# Erica-HAT.net
KiCad netlist of a schematic drawn in EAGLE
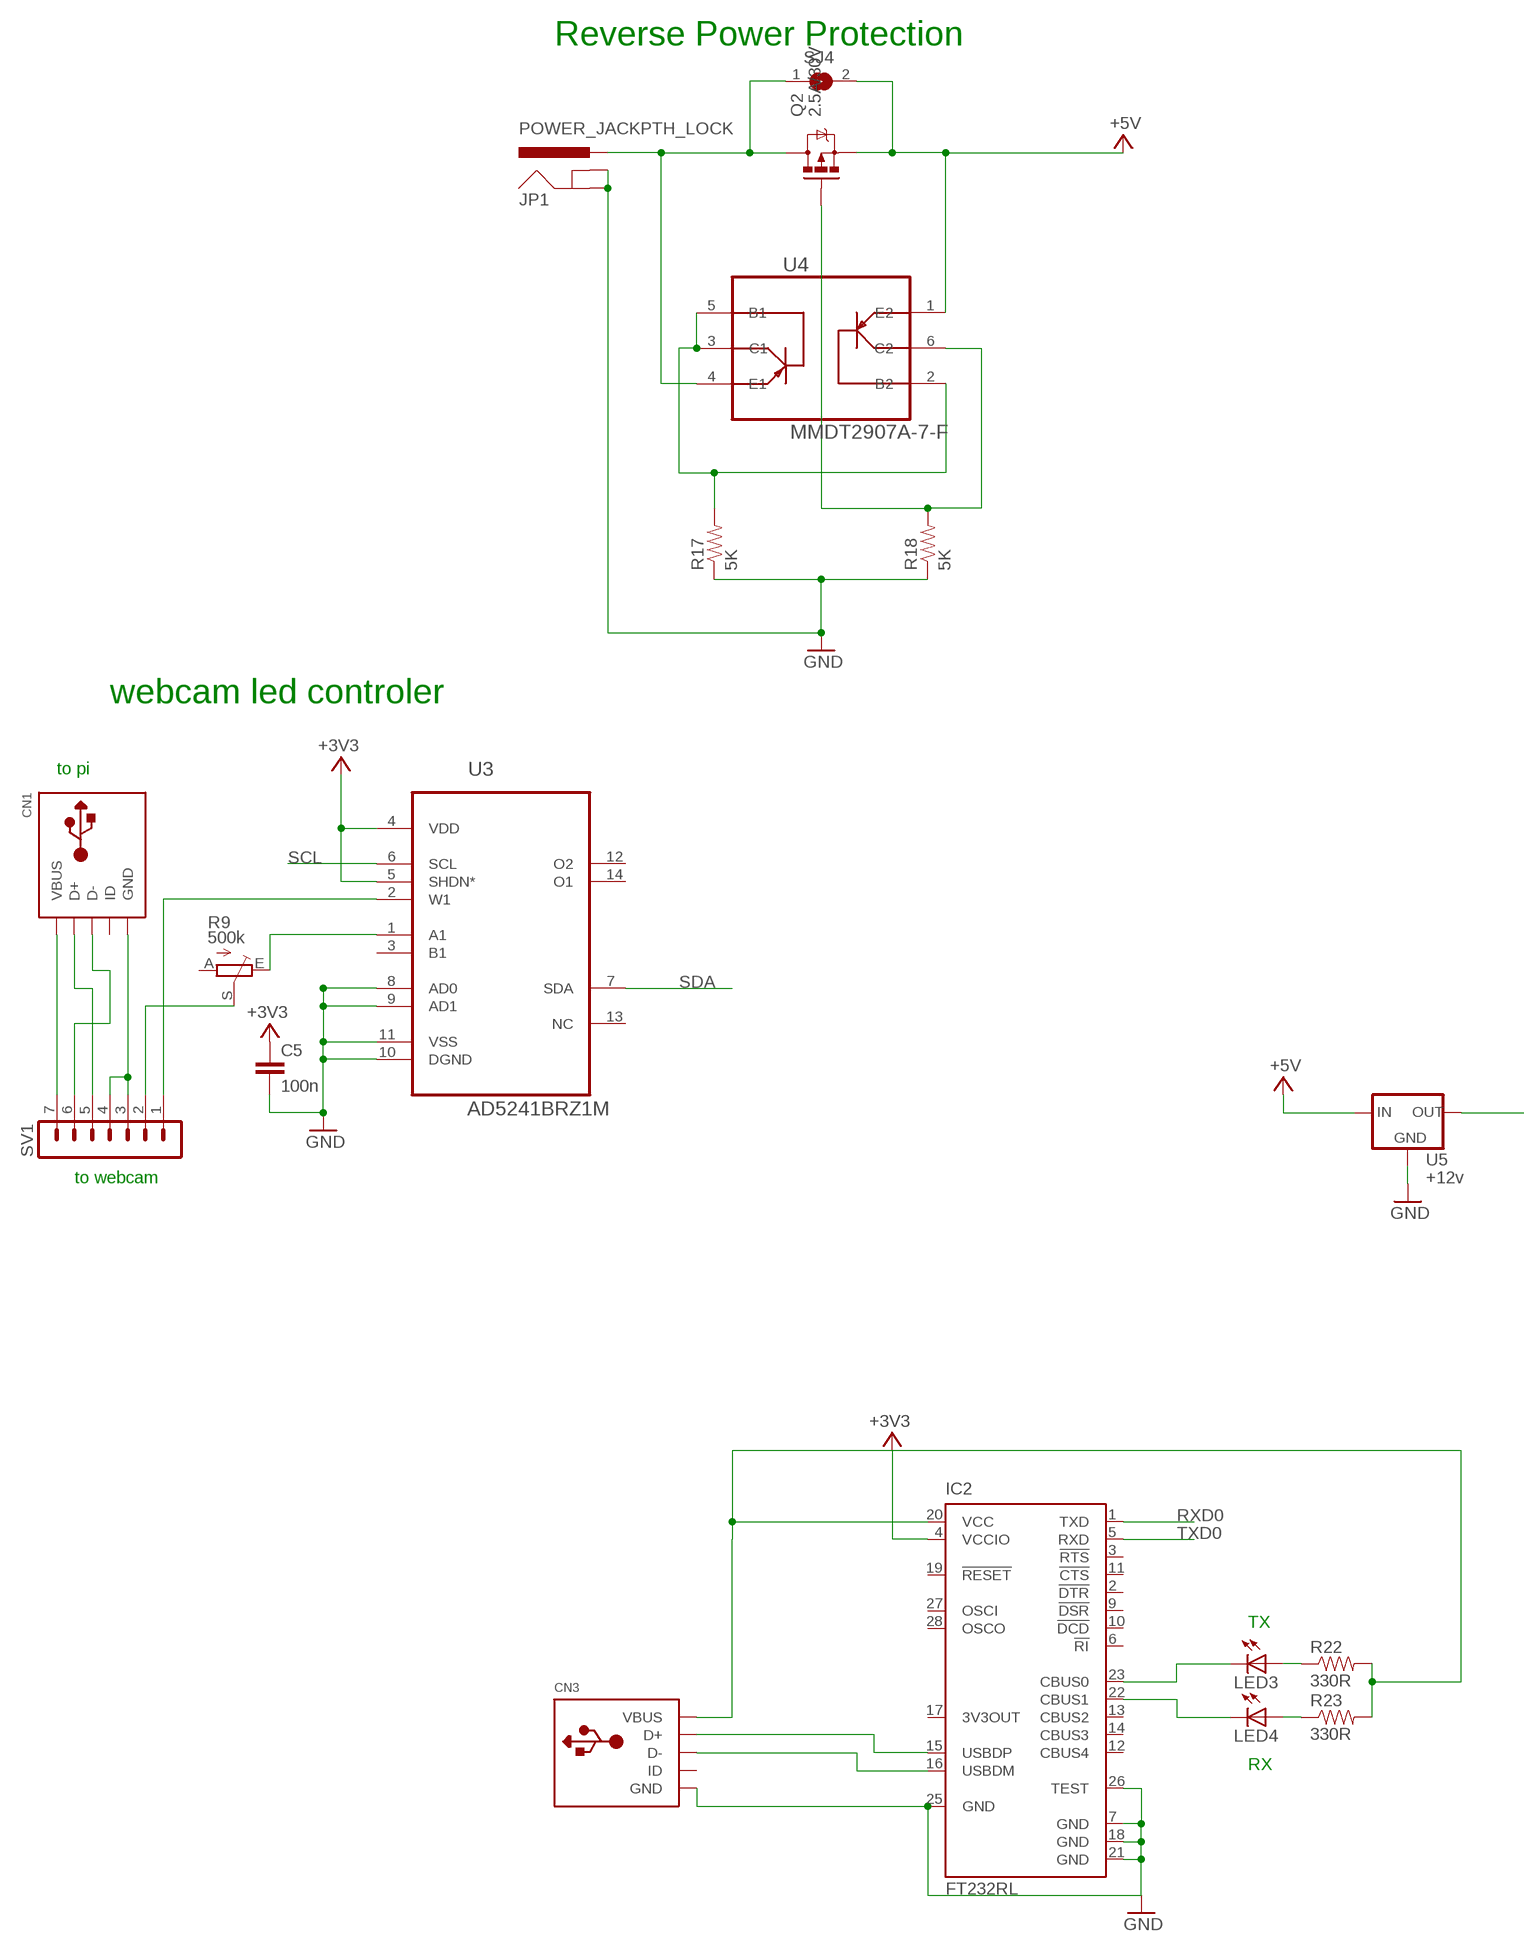
[diagram p0: schematic, sheet 1, part 1 of 2]
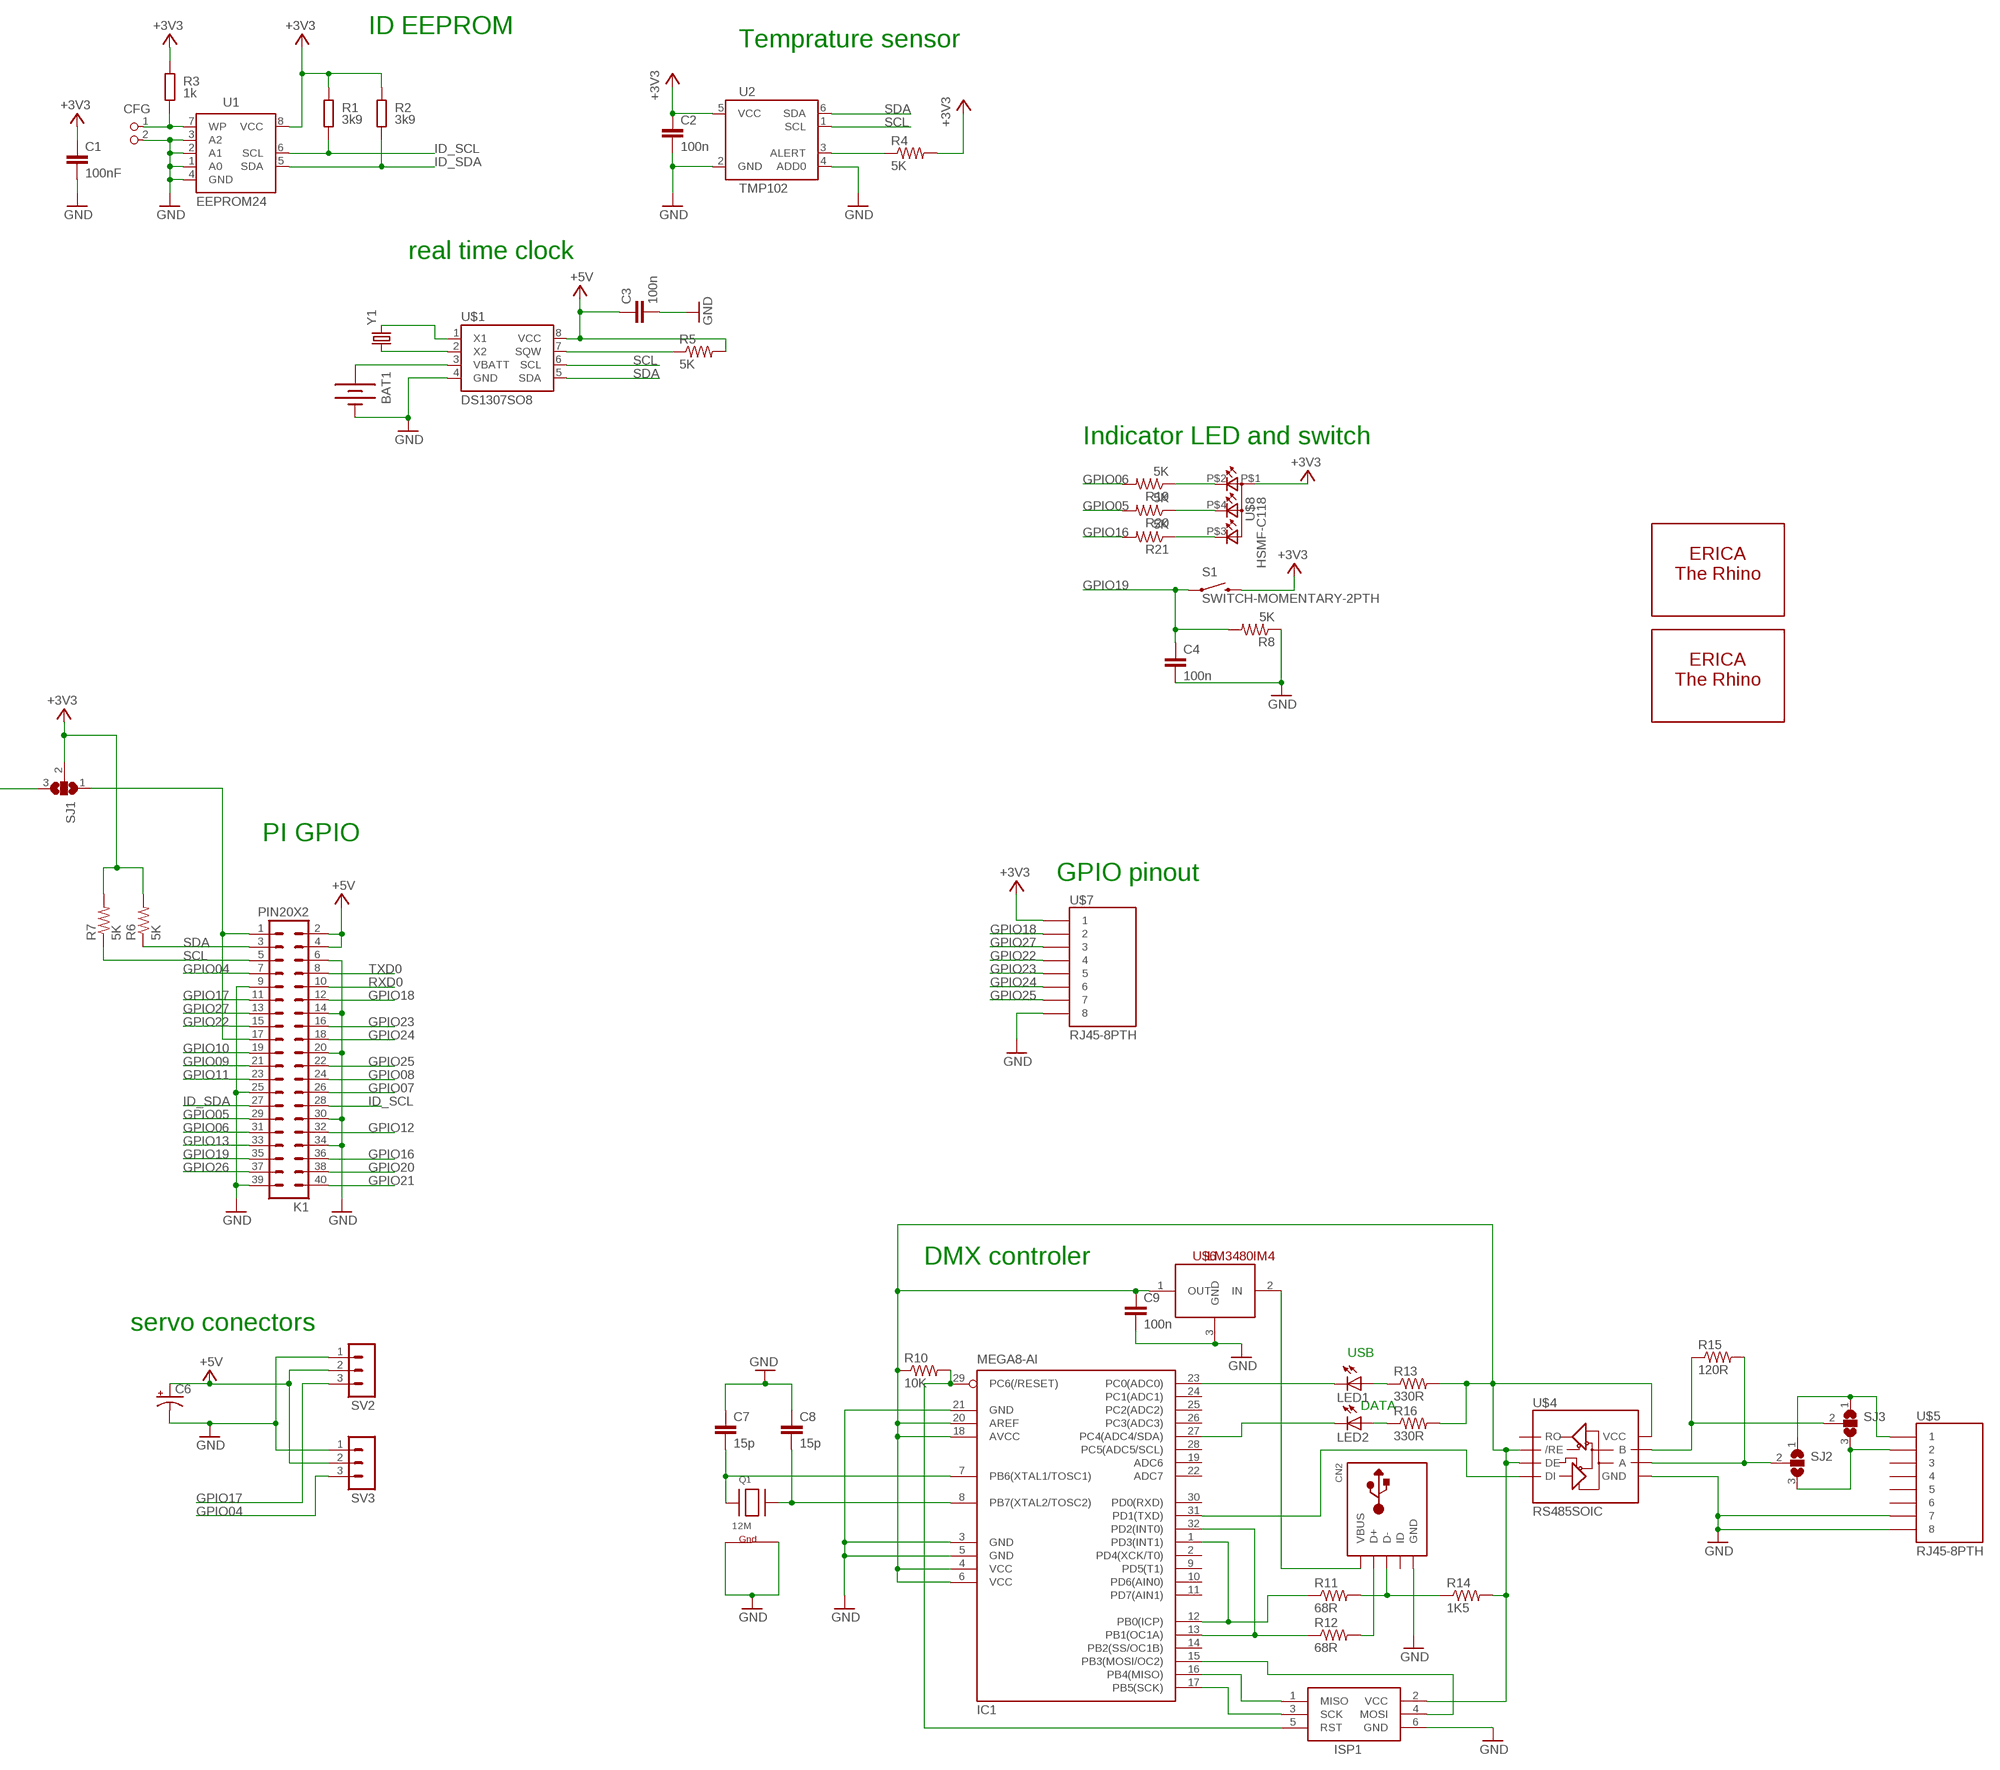
[diagram p1: schematic, sheet 1, part 2 of 2]

(export (version "E")
  (design (tool "Eeschema 10.0.6"))
  (components
    (comp (ref "BAT1")
      (value "BATTERY12MM")
      (footprint "eagle-import:BATTCON_12MM")
      (libsource (lib "eagle-import") (part "BATTERY12MM"))
    )
    (comp (ref "C1")
      (value "100nF")
      (footprint "eagle-import:C0805K")
      (libsource (lib "eagle-import") (part "C-EUC0805K"))
    )
    (comp (ref "C2")
      (value "100n")
      (footprint "eagle-import:0603-CAP")
      (libsource (lib "eagle-import") (part "CAP0603-CAP"))
    )
    (comp (ref "C3")
      (value "100n")
      (footprint "eagle-import:0603-CAP")
      (libsource (lib "eagle-import") (part "CAP0603-CAP"))
    )
    (comp (ref "C4")
      (value "100n")
      (footprint "eagle-import:0603-CAP")
      (libsource (lib "eagle-import") (part "CAP0603-CAP"))
    )
    (comp (ref "C5")
      (value "100n")
      (footprint "eagle-import:0603-CAP")
      (libsource (lib "eagle-import") (part "CAP0603-CAP"))
    )
    (comp (ref "C6")
      (value "CAP_POLPTH2")
      (footprint "eagle-import:CPOL-RADIAL-10UF-25V")
      (libsource (lib "eagle-import") (part "CAP_POLPTH2"))
    )
    (comp (ref "C7")
      (value "15p")
      (footprint "eagle-import:0603-CAP")
      (libsource (lib "eagle-import") (part "CAP0603-CAP"))
    )
    (comp (ref "C8")
      (value "15p")
      (footprint "eagle-import:0603-CAP")
      (libsource (lib "eagle-import") (part "CAP0603-CAP"))
    )
    (comp (ref "C9")
      (value "100n")
      (footprint "eagle-import:0603-CAP")
      (libsource (lib "eagle-import") (part "CAP0603-CAP"))
    )
    (comp (ref "CFG")
      (value "PIN2_100")
      (footprint "eagle-import:PIN_W_2")
      (libsource (lib "eagle-import") (part "PIN2_100"))
    )
    (comp (ref "CN1")
      (value "USBMINIB")
      (footprint "eagle-import:USB-MINIB")
      (libsource (lib "eagle-import") (part "USBMINIB"))
    )
    (comp (ref "CN2")
      (value "USBMINIB")
      (footprint "eagle-import:USB-MINIB")
      (libsource (lib "eagle-import") (part "USBMINIB"))
    )
    (comp (ref "CN3")
      (value "USBMINIB")
      (footprint "eagle-import:USB-MINIB")
      (libsource (lib "eagle-import") (part "USBMINIB"))
    )
    (comp (ref "IC1")
      (value "MEGA8-AI")
      (footprint "eagle-import:TQFP32-08")
      (fields (field (name "MPN") "ATMEGA8-16AU"))
      (libsource (lib "eagle-import") (part "MEGA8-AI"))
    )
    (comp (ref "IC2")
      (value "FT232RL")
      (footprint "eagle-import:SSOP28")
      (libsource (lib "eagle-import") (part "FT232RL"))
    )
    (comp (ref "ISP1")
      (value "AVRISP-6")
      (footprint "eagle-import:AVRISP")
      (libsource (lib "eagle-import") (part "AVRISP-6"))
    )
    (comp (ref "JP1")
      (value "POWER_JACKPTH_LOCK")
      (footprint "eagle-import:POWER_JACK_PTH_LOCK")
      (libsource (lib "eagle-import") (part "POWER_JACKPTH_LOCK"))
    )
    (comp (ref "K1")
      (value "PIN20X2")
      (footprint "eagle-import:PIN_20X2")
      (libsource (lib "eagle-import") (part "PIN20X2"))
    )
    (comp (ref "LED1")
      (value "LEDCHIP-LED0603")
      (footprint "eagle-import:CHIP-LED0603")
      (libsource (lib "eagle-import") (part "LEDCHIP-LED0603"))
    )
    (comp (ref "LED2")
      (value "LEDCHIP-LED0603")
      (footprint "eagle-import:CHIP-LED0603")
      (libsource (lib "eagle-import") (part "LEDCHIP-LED0603"))
    )
    (comp (ref "LED3")
      (value "LEDCHIP-LED0603")
      (footprint "eagle-import:CHIP-LED0603")
      (libsource (lib "eagle-import") (part "LEDCHIP-LED0603"))
    )
    (comp (ref "LED4")
      (value "LEDCHIP-LED0603")
      (footprint "eagle-import:CHIP-LED0603")
      (libsource (lib "eagle-import") (part "LEDCHIP-LED0603"))
    )
    (comp (ref "Q1")
      (value "12M")
      (footprint "eagle-import:NX3225")
      (libsource (lib "eagle-import") (part "XTAL-4-3225"))
    )
    (comp (ref "Q2")
      (value "2.5A/30V")
      (footprint "eagle-import:SOT23-3")
      (libsource (lib "eagle-import") (part "MOSFET-PCHANNELDMG2307L"))
    )
    (comp (ref "R1")
      (value "3k9")
      (footprint "eagle-import:M0805")
      (fields (field (name "TOLERANCE") "5%"))
      (libsource (lib "eagle-import") (part "R-EU_M0805"))
    )
    (comp (ref "R2")
      (value "3k9")
      (footprint "eagle-import:M0805")
      (fields (field (name "TOLERANCE") "5%"))
      (libsource (lib "eagle-import") (part "R-EU_M0805"))
    )
    (comp (ref "R3")
      (value "1k")
      (footprint "eagle-import:M0805")
      (fields (field (name "TOLERANCE") "5%"))
      (libsource (lib "eagle-import") (part "R-EU_M0805"))
    )
    (comp (ref "R4")
      (value "5K")
      (footprint "eagle-import:0603-RES")
      (libsource (lib "eagle-import") (part "RESISTOR0603-RES"))
    )
    (comp (ref "R5")
      (value "5K")
      (footprint "eagle-import:0603-RES")
      (libsource (lib "eagle-import") (part "RESISTOR0603-RES"))
    )
    (comp (ref "R6")
      (value "5K")
      (footprint "eagle-import:0603-RES")
      (libsource (lib "eagle-import") (part "RESISTOR0603-RES"))
    )
    (comp (ref "R7")
      (value "5K")
      (footprint "eagle-import:0603-RES")
      (libsource (lib "eagle-import") (part "RESISTOR0603-RES"))
    )
    (comp (ref "R8")
      (value "5K")
      (footprint "eagle-import:0603-RES")
      (libsource (lib "eagle-import") (part "RESISTOR0603-RES"))
    )
    (comp (ref "R9")
      (value "500k")
      (footprint "eagle-import:B25U")
      (libsource (lib "eagle-import") (part "TRIM_EU-B25U"))
    )
    (comp (ref "R10")
      (value "10K")
      (footprint "eagle-import:0603-RES")
      (libsource (lib "eagle-import") (part "RESISTOR0603-RES"))
    )
    (comp (ref "R11")
      (value "68R")
      (footprint "eagle-import:0603-RES")
      (libsource (lib "eagle-import") (part "RESISTOR0603-RES"))
    )
    (comp (ref "R12")
      (value "68R")
      (footprint "eagle-import:0603-RES")
      (libsource (lib "eagle-import") (part "RESISTOR0603-RES"))
    )
    (comp (ref "R13")
      (value "330R")
      (footprint "eagle-import:0603-RES")
      (libsource (lib "eagle-import") (part "RESISTOR0603-RES"))
    )
    (comp (ref "R14")
      (value "1K5")
      (footprint "eagle-import:0603-RES")
      (libsource (lib "eagle-import") (part "RESISTOR0603-RES"))
    )
    (comp (ref "R15")
      (value "120R")
      (footprint "eagle-import:0603-RES")
      (libsource (lib "eagle-import") (part "RESISTOR0603-RES"))
    )
    (comp (ref "R16")
      (value "330R")
      (footprint "eagle-import:0603-RES")
      (libsource (lib "eagle-import") (part "RESISTOR0603-RES"))
    )
    (comp (ref "R17")
      (value "5K")
      (footprint "eagle-import:0603-RES")
      (libsource (lib "eagle-import") (part "RESISTOR0603-RES"))
    )
    (comp (ref "R18")
      (value "5K")
      (footprint "eagle-import:0603-RES")
      (libsource (lib "eagle-import") (part "RESISTOR0603-RES"))
    )
    (comp (ref "R19")
      (value "5K")
      (footprint "eagle-import:0603-RES")
      (libsource (lib "eagle-import") (part "RESISTOR0603-RES"))
    )
    (comp (ref "R20")
      (value "5K")
      (footprint "eagle-import:0603-RES")
      (libsource (lib "eagle-import") (part "RESISTOR0603-RES"))
    )
    (comp (ref "R21")
      (value "5K")
      (footprint "eagle-import:0603-RES")
      (libsource (lib "eagle-import") (part "RESISTOR0603-RES"))
    )
    (comp (ref "R22")
      (value "330R")
      (footprint "eagle-import:0603-RES")
      (libsource (lib "eagle-import") (part "RESISTOR0603-RES"))
    )
    (comp (ref "R23")
      (value "330R")
      (footprint "eagle-import:0603-RES")
      (libsource (lib "eagle-import") (part "RESISTOR0603-RES"))
    )
    (comp (ref "S1")
      (value "SWITCH-MOMENTARY-2PTH")
      (footprint "eagle-import:TACTILE-PTH")
      (libsource (lib "eagle-import") (part "SWITCH-MOMENTARY-2PTH"))
    )
    (comp (ref "SJ1")
      (value "SJ2W")
      (footprint "eagle-import:SJ_2")
      (libsource (lib "eagle-import") (part "SJ2W"))
    )
    (comp (ref "SJ2")
      (value "SJ2W")
      (footprint "eagle-import:SJ_2")
      (libsource (lib "eagle-import") (part "SJ2W"))
    )
    (comp (ref "SJ3")
      (value "SJ2W")
      (footprint "eagle-import:SJ_2")
      (libsource (lib "eagle-import") (part "SJ2W"))
    )
    (comp (ref "SJ4") (value "SJ") (footprint "eagle-import:SJ") (libsource (lib "eagle-import") (part "SJ")))
    (comp (ref "SV1")
      (value "MA07-1")
      (footprint "eagle-import:MA07-1")
      (libsource (lib "eagle-import") (part "MA07-1"))
    )
    (comp (ref "SV2")
      (value "MA03-1")
      (footprint "eagle-import:MA03-1")
      (libsource (lib "eagle-import") (part "MA03-1"))
    )
    (comp (ref "SV3")
      (value "MA03-1")
      (footprint "eagle-import:MA03-1")
      (libsource (lib "eagle-import") (part "MA03-1"))
    )
    (comp (ref "U$1")
      (value "DS1307SO8")
      (footprint "eagle-import:SO08")
      (libsource (lib "eagle-import") (part "DS1307SO8"))
    )
    (comp (ref "U$2")
      (value "ERICALOGO")
      (footprint "eagle-import:ERICA_LOGO")
      (libsource (lib "eagle-import") (part "ERICALOGO"))
    )
    (comp (ref "U$3")
      (value "ERICASILHOUETTE")
      (footprint "eagle-import:ERICA_SILHOUETTE")
      (libsource (lib "eagle-import") (part "ERICASILHOUETTE"))
    )
    (comp (ref "U$4")
      (value "RS485SOIC")
      (footprint "eagle-import:SO08")
      (libsource (lib "eagle-import") (part "RS485SOIC"))
    )
    (comp (ref "U$5")
      (value "RJ45-8PTH")
      (footprint "eagle-import:RJ45-8")
      (libsource (lib "eagle-import") (part "RJ45-8PTH"))
    )
    (comp (ref "U$6")
      (value "LM3480IM4")
      (footprint "eagle-import:SOT23-3")
      (libsource (lib "eagle-import") (part "LM3480IM4"))
    )
    (comp (ref "U$7")
      (value "RJ45-8PTH")
      (footprint "eagle-import:RJ45-8")
      (libsource (lib "eagle-import") (part "RJ45-8PTH"))
    )
    (comp (ref "U$8")
      (value "HSMF-C118")
      (footprint "eagle-import:HSMF-C118")
      (libsource (lib "eagle-import") (part "HSMF-C118"))
    )
    (comp (ref "U1")
      (value "EEPROM24")
      (footprint "eagle-import:SOIC8")
      (libsource (lib "eagle-import") (part "EEPROM24"))
    )
    (comp (ref "U2")
      (value "TMP102")
      (footprint "eagle-import:SOT563")
      (libsource (lib "eagle-import") (part "TMP102"))
    )
    (comp (ref "U3")
      (value "AD5241BRZ1M")
      (footprint "eagle-import:SOIC127P600X175-14N")
      (libsource (lib "eagle-import") (part "AD5241BRZ1M"))
    )
    (comp (ref "U4")
      (value "MMDT2907A-7-F")
      (footprint "eagle-import:SOT65P210X110-6N")
      (libsource (lib "eagle-import") (part "MMDT2907A-7-F"))
    )
    (comp (ref "U5")
      (value "+12v")
      (footprint "eagle-import:SOT223")
      (libsource (lib "eagle-import") (part "V_REG_MIC2920"))
    )
    (comp (ref "Y1")
      (value "CRYSTAL32-SMD")
      (footprint "eagle-import:CRYSTAL-32KHZ-SMD")
      (libsource (lib "eagle-import") (part "CRYSTAL32-SMD"))
    )
  )
  (nets
    (net (code "1") (name "+3V3") (class "Default")
      (node (ref "C1") (pin "1") (pinfunction "1_1") (pintype "passive"))
      (node (ref "C2") (pin "1") (pinfunction "1_1") (pintype "passive"))
      (node (ref "C5") (pin "1") (pinfunction "1_1") (pintype "passive"))
      (node (ref "IC2") (pin "4") (pinfunction "VCCIO_4") (pintype "power_in"))
      (node (ref "R1") (pin "2") (pinfunction "2_2") (pintype "passive"))
      (node (ref "R2") (pin "2") (pinfunction "2_2") (pintype "passive"))
      (node (ref "R3") (pin "2") (pinfunction "2_2") (pintype "passive"))
      (node (ref "R4") (pin "2") (pinfunction "2_2") (pintype "passive"))
      (node (ref "R6") (pin "2") (pinfunction "2_2") (pintype "passive"))
      (node (ref "R7") (pin "2") (pinfunction "2_2") (pintype "passive"))
      (node (ref "S1") (pin "3") (pinfunction "2_3") (pintype "passive"))
      (node (ref "SJ1") (pin "2") (pinfunction "2_2") (pintype "passive"))
      (node (ref "U$7") (pin "1") (pinfunction "1_1") (pintype "bidirectional"))
      (node (ref "U$8") (pin "P$1") (pinfunction "A2_P$1") (pintype "passive"))
      (node (ref "U1") (pin "8") (pinfunction "VCC_8") (pintype "power_in"))
      (node (ref "U2") (pin "5") (pinfunction "VCC_5") (pintype "bidirectional"))
      (node (ref "U3") (pin "4") (pinfunction "VDD_4") (pintype "power_in"))
      (node (ref "U3") (pin "5") (pinfunction "SHDN*_5") (pintype "passive"))
    )
    (net (code "2") (name "+5V") (class "Default")
      (node (ref "C3") (pin "1") (pinfunction "1_1") (pintype "passive"))
      (node (ref "C6") (pin "1") (pinfunction "+_1") (pintype "passive"))
      (node (ref "K1") (pin "2") (pinfunction "2_2") (pintype "passive"))
      (node (ref "K1") (pin "4") (pinfunction "4_4") (pintype "passive"))
      (node (ref "Q2") (pin "2") (pinfunction "S_2") (pintype "passive"))
      (node (ref "R5") (pin "2") (pinfunction "2_2") (pintype "passive"))
      (node (ref "SJ4") (pin "2") (pinfunction "2_2") (pintype "passive"))
      (node (ref "SV2") (pin "2") (pinfunction "2_2") (pintype "passive"))
      (node (ref "SV3") (pin "2") (pinfunction "2_2") (pintype "passive"))
      (node (ref "U$1") (pin "8") (pinfunction "VCC_8") (pintype "bidirectional"))
      (node (ref "U4") (pin "1") (pinfunction "E2_1") (pintype "passive"))
      (node (ref "U5") (pin "1") (pinfunction "IN_1") (pintype "input"))
    )
    (net (code "3") (name "/GPIO04") (class "Default")
      (node (ref "K1") (pin "7") (pinfunction "7_7") (pintype "passive"))
      (node (ref "SV3") (pin "3") (pinfunction "3_3") (pintype "passive"))
    )
    (net (code "4") (name "/GPIO05") (class "Default")
      (node (ref "K1") (pin "29") (pinfunction "29_29") (pintype "passive"))
      (node (ref "R20") (pin "2") (pinfunction "2_2") (pintype "passive"))
    )
    (net (code "5") (name "/GPIO06") (class "Default")
      (node (ref "K1") (pin "31") (pinfunction "31_31") (pintype "passive"))
      (node (ref "R19") (pin "2") (pinfunction "2_2") (pintype "passive"))
    )
    (net (code "6") (name "/GPIO07") (class "Default")
      (node (ref "K1") (pin "26") (pinfunction "26_26") (pintype "passive"))
    )
    (net (code "7") (name "/GPIO08") (class "Default")
      (node (ref "K1") (pin "24") (pinfunction "24_24") (pintype "passive"))
    )
    (net (code "8") (name "/GPIO09") (class "Default")
      (node (ref "K1") (pin "21") (pinfunction "21_21") (pintype "passive"))
    )
    (net (code "9") (name "/GPIO10") (class "Default")
      (node (ref "K1") (pin "19") (pinfunction "19_19") (pintype "passive"))
    )
    (net (code "10") (name "/GPIO11") (class "Default")
      (node (ref "K1") (pin "23") (pinfunction "23_23") (pintype "passive"))
    )
    (net (code "11") (name "/GPIO12") (class "Default")
      (node (ref "K1") (pin "32") (pinfunction "32_32") (pintype "passive"))
    )
    (net (code "12") (name "/GPIO13") (class "Default")
      (node (ref "K1") (pin "33") (pinfunction "33_33") (pintype "passive"))
    )
    (net (code "13") (name "/GPIO16") (class "Default")
      (node (ref "K1") (pin "36") (pinfunction "36_36") (pintype "passive"))
      (node (ref "R21") (pin "2") (pinfunction "2_2") (pintype "passive"))
    )
    (net (code "14") (name "/GPIO17") (class "Default")
      (node (ref "K1") (pin "11") (pinfunction "11_11") (pintype "passive"))
      (node (ref "SV2") (pin "3") (pinfunction "3_3") (pintype "passive"))
    )
    (net (code "15") (name "/GPIO18") (class "Default")
      (node (ref "K1") (pin "12") (pinfunction "12_12") (pintype "passive"))
      (node (ref "U$7") (pin "2") (pinfunction "2_2") (pintype "bidirectional"))
    )
    (net (code "16") (name "/GPIO19") (class "Default")
      (node (ref "C4") (pin "1") (pinfunction "1_1") (pintype "passive"))
      (node (ref "K1") (pin "35") (pinfunction "35_35") (pintype "passive"))
      (node (ref "R8") (pin "2") (pinfunction "2_2") (pintype "passive"))
      (node (ref "S1") (pin "1") (pinfunction "1_1") (pintype "passive"))
    )
    (net (code "17") (name "/GPIO20") (class "Default")
      (node (ref "K1") (pin "38") (pinfunction "38_38") (pintype "passive"))
    )
    (net (code "18") (name "/GPIO21") (class "Default")
      (node (ref "K1") (pin "40") (pinfunction "40_40") (pintype "passive"))
    )
    (net (code "19") (name "/GPIO22") (class "Default")
      (node (ref "K1") (pin "15") (pinfunction "15_15") (pintype "passive"))
      (node (ref "U$7") (pin "4") (pinfunction "4_4") (pintype "bidirectional"))
    )
    (net (code "20") (name "/GPIO23") (class "Default")
      (node (ref "K1") (pin "16") (pinfunction "16_16") (pintype "passive"))
      (node (ref "U$7") (pin "5") (pinfunction "5_5") (pintype "bidirectional"))
    )
    (net (code "21") (name "/GPIO24") (class "Default")
      (node (ref "K1") (pin "18") (pinfunction "18_18") (pintype "passive"))
      (node (ref "U$7") (pin "6") (pinfunction "6_6") (pintype "bidirectional"))
    )
    (net (code "22") (name "/GPIO25") (class "Default")
      (node (ref "K1") (pin "22") (pinfunction "22_22") (pintype "passive"))
      (node (ref "U$7") (pin "7") (pinfunction "7_7") (pintype "bidirectional"))
    )
    (net (code "23") (name "/GPIO26") (class "Default")
      (node (ref "K1") (pin "37") (pinfunction "37_37") (pintype "passive"))
    )
    (net (code "24") (name "/GPIO27") (class "Default")
      (node (ref "K1") (pin "13") (pinfunction "13_13") (pintype "passive"))
      (node (ref "U$7") (pin "3") (pinfunction "3_3") (pintype "bidirectional"))
    )
    (net (code "25") (name "/ID_SCL") (class "Default")
      (node (ref "K1") (pin "28") (pinfunction "28_28") (pintype "passive"))
      (node (ref "R1") (pin "1") (pinfunction "1_1") (pintype "passive"))
      (node (ref "U1") (pin "6") (pinfunction "SCL_6") (pintype "input"))
    )
    (net (code "26") (name "/ID_SDA") (class "Default")
      (node (ref "K1") (pin "27") (pinfunction "27_27") (pintype "passive"))
      (node (ref "R2") (pin "1") (pinfunction "1_1") (pintype "passive"))
      (node (ref "U1") (pin "5") (pinfunction "SDA_5") (pintype "bidirectional"))
    )
    (net (code "27") (name "/RXD0") (class "Default")
      (node (ref "IC2") (pin "1") (pinfunction "TXD_1") (pintype "output"))
      (node (ref "K1") (pin "10") (pinfunction "10_10") (pintype "passive"))
    )
    (net (code "28") (name "/SCL") (class "Default")
      (node (ref "K1") (pin "5") (pinfunction "5_5") (pintype "passive"))
      (node (ref "R7") (pin "1") (pinfunction "1_1") (pintype "passive"))
      (node (ref "U$1") (pin "6") (pinfunction "SCL_6") (pintype "bidirectional"))
      (node (ref "U2") (pin "1") (pinfunction "SCL_1") (pintype "bidirectional"))
      (node (ref "U3") (pin "6") (pinfunction "SCL_6") (pintype "passive"))
    )
    (net (code "29") (name "/SDA") (class "Default")
      (node (ref "K1") (pin "3") (pinfunction "3_3") (pintype "passive"))
      (node (ref "R6") (pin "1") (pinfunction "1_1") (pintype "passive"))
      (node (ref "U$1") (pin "5") (pinfunction "SDA_5") (pintype "bidirectional"))
      (node (ref "U2") (pin "6") (pinfunction "SDA_6") (pintype "bidirectional"))
      (node (ref "U3") (pin "7") (pinfunction "SDA_7") (pintype "passive"))
    )
    (net (code "30") (name "/TXD0") (class "Default")
      (node (ref "IC2") (pin "5") (pinfunction "RXD_5") (pintype "input"))
      (node (ref "K1") (pin "8") (pinfunction "8_8") (pintype "passive"))
    )
    (net (code "31") (name "GND") (class "Default")
      (node (ref "BAT1") (pin "GND") (pinfunction "-_GND") (pintype "power_in"))
      (node (ref "C1") (pin "2") (pinfunction "2_2") (pintype "passive"))
      (node (ref "C2") (pin "2") (pinfunction "2_2") (pintype "passive"))
      (node (ref "C3") (pin "2") (pinfunction "2_2") (pintype "passive"))
      (node (ref "C4") (pin "2") (pinfunction "2_2") (pintype "passive"))
      (node (ref "C5") (pin "2") (pinfunction "2_2") (pintype "passive"))
      (node (ref "C6") (pin "2") (pinfunction "-_2") (pintype "passive"))
      (node (ref "C7") (pin "1") (pinfunction "1_1") (pintype "passive"))
      (node (ref "C8") (pin "1") (pinfunction "1_1") (pintype "passive"))
      (node (ref "C9") (pin "2") (pinfunction "2_2") (pintype "passive"))
      (node (ref "CFG") (pin "2") (pinfunction "2_2") (pintype "passive"))
      (node (ref "CN2") (pin "GND") (pinfunction "GND_GND") (pintype "power_in"))
      (node (ref "CN3") (pin "GND") (pinfunction "GND_GND") (pintype "power_in"))
      (node (ref "IC1") (pin "21") (pinfunction "GND_21") (pintype "power_in"))
      (node (ref "IC1") (pin "3") (pinfunction "GND_3") (pintype "power_in"))
      (node (ref "IC1") (pin "5") (pinfunction "GND_5") (pintype "power_in"))
      (node (ref "IC2") (pin "18") (pinfunction "GND_18") (pintype "power_in"))
      (node (ref "IC2") (pin "21") (pinfunction "GND_21") (pintype "power_in"))
      (node (ref "IC2") (pin "25") (pinfunction "GND_25") (pintype "power_in"))
      (node (ref "IC2") (pin "26") (pinfunction "TEST_26") (pintype "input"))
      (node (ref "IC2") (pin "7") (pinfunction "GND_7") (pintype "power_in"))
      (node (ref "ISP1") (pin "6") (pinfunction "GND_6") (pintype "power_in"))
      (node (ref "JP1") (pin "GND") (pinfunction "GND_GND") (pintype "bidirectional"))
      (node (ref "JP1") (pin "GNDBREAK") (pinfunction "GNDBREAK_GNDBREAK") (pintype "bidirectional"))
      (node (ref "K1") (pin "14") (pinfunction "14_14") (pintype "passive"))
      (node (ref "K1") (pin "20") (pinfunction "20_20") (pintype "passive"))
      (node (ref "K1") (pin "25") (pinfunction "25_25") (pintype "passive"))
      (node (ref "K1") (pin "30") (pinfunction "30_30") (pintype "passive"))
      (node (ref "K1") (pin "34") (pinfunction "34_34") (pintype "passive"))
      (node (ref "K1") (pin "39") (pinfunction "39_39") (pintype "passive"))
      (node (ref "K1") (pin "6") (pinfunction "6_6") (pintype "passive"))
      (node (ref "K1") (pin "9") (pinfunction "9_9") (pintype "passive"))
      (node (ref "Q1") (pin "2") (pinfunction "G1_2") (pintype "power_in"))
      (node (ref "Q1") (pin "4") (pinfunction "G2_4") (pintype "power_in"))
      (node (ref "R17") (pin "1") (pinfunction "1_1") (pintype "passive"))
      (node (ref "R18") (pin "1") (pinfunction "1_1") (pintype "passive"))
      (node (ref "R8") (pin "1") (pinfunction "1_1") (pintype "passive"))
      (node (ref "SV2") (pin "1") (pinfunction "1_1") (pintype "passive"))
      (node (ref "SV3") (pin "1") (pinfunction "1_1") (pintype "passive"))
      (node (ref "U$1") (pin "4") (pinfunction "GND_4") (pintype "bidirectional"))
      (node (ref "U$4") (pin "5") (pinfunction "GND_5") (pintype "bidirectional"))
      (node (ref "U$5") (pin "7") (pinfunction "7_7") (pintype "bidirectional"))
      (node (ref "U$5") (pin "8") (pinfunction "8_8") (pintype "bidirectional"))
      (node (ref "U$6") (pin "3") (pinfunction "GND_3") (pintype "bidirectional"))
      (node (ref "U$7") (pin "8") (pinfunction "8_8") (pintype "bidirectional"))
      (node (ref "U1") (pin "1") (pinfunction "A0_1") (pintype "input"))
      (node (ref "U1") (pin "2") (pinfunction "A1_2") (pintype "input"))
      (node (ref "U1") (pin "3") (pinfunction "A2_3") (pintype "input"))
      (node (ref "U1") (pin "4") (pinfunction "GND_4") (pintype "power_in"))
      (node (ref "U2") (pin "2") (pinfunction "GND_2") (pintype "bidirectional"))
      (node (ref "U2") (pin "4") (pinfunction "ADD0_4") (pintype "bidirectional"))
      (node (ref "U3") (pin "10") (pinfunction "DGND_10") (pintype "passive"))
      (node (ref "U3") (pin "11") (pinfunction "VSS_11") (pintype "power_in"))
      (node (ref "U3") (pin "8") (pinfunction "AD0_8") (pintype "passive"))
      (node (ref "U3") (pin "9") (pinfunction "AD1_9") (pintype "passive"))
      (node (ref "U5") (pin "2") (pinfunction "GND_2") (pintype "input"))
    )
    (net (code "32") (name "Net-(BAT1-+)") (class "Default")
      (node (ref "BAT1") (pin "PWR@1") (pinfunction "+_PWR@1") (pintype "power_in"))
      (node (ref "U$1") (pin "3") (pinfunction "VBATT_3") (pintype "bidirectional"))
    )
    (net (code "33") (name "Net-(CN1-PadD+)") (class "Default")
      (node (ref "CN1") (pin "D+") (pinfunction "D+_D+") (pintype "bidirectional"))
      (node (ref "SV1") (pin "5") (pinfunction "5_5") (pintype "passive"))
    )
    (net (code "34") (name "Net-(CN1-PadD-)") (class "Default")
      (node (ref "CN1") (pin "D-") (pinfunction "D-_D-") (pintype "bidirectional"))
      (node (ref "SV1") (pin "6") (pinfunction "6_6") (pintype "passive"))
    )
    (net (code "35") (name "Net-(CN1-PadGND)") (class "Default")
      (node (ref "CN1") (pin "GND") (pinfunction "GND_GND") (pintype "power_in"))
      (node (ref "SV1") (pin "3") (pinfunction "3_3") (pintype "passive"))
      (node (ref "SV1") (pin "4") (pinfunction "4_4") (pintype "passive"))
    )
    (net (code "36") (name "Net-(CN1-PadVBUS)") (class "Default")
      (node (ref "CN1") (pin "VBUS") (pinfunction "VBUS_VBUS") (pintype "power_in"))
      (node (ref "SV1") (pin "7") (pinfunction "7_7") (pintype "passive"))
    )
    (net (code "37") (name "Net-(CN2-PadD+)") (class "Default")
      (node (ref "CN2") (pin "D+") (pinfunction "D+_D+") (pintype "bidirectional"))
      (node (ref "R12") (pin "2") (pinfunction "2_2") (pintype "passive"))
    )
    (net (code "38") (name "Net-(CN2-PadD-)") (class "Default")
      (node (ref "CN2") (pin "D-") (pinfunction "D-_D-") (pintype "bidirectional"))
      (node (ref "R11") (pin "2") (pinfunction "2_2") (pintype "passive"))
      (node (ref "R14") (pin "1") (pinfunction "1_1") (pintype "passive"))
    )
    (net (code "39") (name "Net-(IC1-AREF)") (class "Default")
      (node (ref "C9") (pin "1") (pinfunction "1_1") (pintype "passive"))
      (node (ref "IC1") (pin "18") (pinfunction "AVCC_18") (pintype "power_in"))
      (node (ref "IC1") (pin "20") (pinfunction "AREF_20") (pintype "passive"))
      (node (ref "IC1") (pin "4") (pinfunction "VCC_4") (pintype "power_in"))
      (node (ref "IC1") (pin "6") (pinfunction "VCC_6") (pintype "power_in"))
      (node (ref "ISP1") (pin "2") (pinfunction "VCC_2") (pintype "power_in"))
      (node (ref "R10") (pin "1") (pinfunction "1_1") (pintype "passive"))
      (node (ref "R13") (pin "2") (pinfunction "2_2") (pintype "passive"))
      (node (ref "R14") (pin "2") (pinfunction "2_2") (pintype "passive"))
      (node (ref "R16") (pin "2") (pinfunction "2_2") (pintype "passive"))
      (node (ref "U$4") (pin "2") (pinfunction "/RE_2") (pintype "bidirectional"))
      (node (ref "U$4") (pin "3") (pinfunction "DE_3") (pintype "bidirectional"))
      (node (ref "U$4") (pin "8") (pinfunction "VCC_8") (pintype "bidirectional"))
      (node (ref "U$6") (pin "1") (pinfunction "OUT_1") (pintype "bidirectional"))
    )
    (net (code "40") (name "Net-(IC1-PB0(ICP))") (class "Default")
      (node (ref "IC1") (pin "1") (pinfunction "PD3(INT1)_1") (pintype "bidirectional"))
      (node (ref "IC1") (pin "12") (pinfunction "PB0(ICP)_12") (pintype "bidirectional"))
      (node (ref "R11") (pin "1") (pinfunction "1_1") (pintype "passive"))
    )
    (net (code "41") (name "Net-(IC1-PB1(OC1A))") (class "Default")
      (node (ref "IC1") (pin "13") (pinfunction "PB1(OC1A)_13") (pintype "bidirectional"))
      (node (ref "IC1") (pin "32") (pinfunction "PD2(INT0)_32") (pintype "bidirectional"))
      (node (ref "R12") (pin "1") (pinfunction "1_1") (pintype "passive"))
    )
    (net (code "42") (name "Net-(IC1-PB3(MOSI{slash}OC2))") (class "Default")
      (node (ref "IC1") (pin "15") (pinfunction "PB3(MOSI/OC2)_15") (pintype "bidirectional"))
      (node (ref "ISP1") (pin "4") (pinfunction "MOSI_4") (pintype "output"))
    )
    (net (code "43") (name "Net-(IC1-PB4(MISO))") (class "Default")
      (node (ref "IC1") (pin "16") (pinfunction "PB4(MISO)_16") (pintype "bidirectional"))
      (node (ref "ISP1") (pin "1") (pinfunction "MISO_1") (pintype "input"))
    )
    (net (code "44") (name "Net-(IC1-PB5(SCK))") (class "Default")
      (node (ref "IC1") (pin "17") (pinfunction "PB5(SCK)_17") (pintype "bidirectional"))
      (node (ref "ISP1") (pin "3") (pinfunction "SCK_3") (pintype "output"))
    )
    (net (code "45") (name "Net-(IC1-PB6(XTAL1{slash}TOSC1))") (class "Default")
      (node (ref "C7") (pin "2") (pinfunction "2_2") (pintype "passive"))
      (node (ref "IC1") (pin "7") (pinfunction "PB6(XTAL1/TOSC1)_7") (pintype "bidirectional"))
      (node (ref "Q1") (pin "1") (pinfunction "X1_1") (pintype "bidirectional"))
    )
    (net (code "46") (name "Net-(IC1-PB7(XTAL2{slash}TOSC2))") (class "Default")
      (node (ref "C8") (pin "2") (pinfunction "2_2") (pintype "passive"))
      (node (ref "IC1") (pin "8") (pinfunction "PB7(XTAL2/TOSC2)_8") (pintype "bidirectional"))
      (node (ref "Q1") (pin "3") (pinfunction "X2_3") (pintype "bidirectional"))
    )
    (net (code "47") (name "Net-(IC1-PC0(ADC0))") (class "Default")
      (node (ref "IC1") (pin "23") (pinfunction "PC0(ADC0)_23") (pintype "bidirectional"))
      (node (ref "LED1") (pin "C") (pinfunction "C_C") (pintype "passive"))
    )
    (net (code "48") (name "Net-(IC1-PC4(ADC4{slash}SDA))") (class "Default")
      (node (ref "IC1") (pin "27") (pinfunction "PC4(ADC4/SDA)_27") (pintype "bidirectional"))
      (node (ref "LED2") (pin "C") (pinfunction "C_C") (pintype "passive"))
    )
    (net (code "49") (name "Net-(IC1-PC6({slash}RESET))") (class "Default")
      (node (ref "IC1") (pin "29") (pinfunction "PC6(/RESET)_29") (pintype "bidirectional"))
      (node (ref "ISP1") (pin "5") (pinfunction "RST_5") (pintype "output"))
      (node (ref "R10") (pin "2") (pinfunction "2_2") (pintype "passive"))
    )
    (net (code "50") (name "Net-(IC1-PD1(TXD))") (class "Default")
      (node (ref "IC1") (pin "31") (pinfunction "PD1(TXD)_31") (pintype "bidirectional"))
      (node (ref "U$4") (pin "4") (pinfunction "DI_4") (pintype "bidirectional"))
    )
    (net (code "51") (name "Net-(IC2-CBUS0)") (class "Default")
      (node (ref "IC2") (pin "23") (pinfunction "CBUS0_23") (pintype "bidirectional"))
      (node (ref "LED3") (pin "C") (pinfunction "C_C") (pintype "passive"))
    )
    (net (code "52") (name "Net-(IC2-CBUS1)") (class "Default")
      (node (ref "IC2") (pin "22") (pinfunction "CBUS1_22") (pintype "bidirectional"))
      (node (ref "LED4") (pin "C") (pinfunction "C_C") (pintype "passive"))
    )
    (net (code "53") (name "Net-(IC2-USBDM)") (class "Default")
      (node (ref "CN3") (pin "D-") (pinfunction "D-_D-") (pintype "bidirectional"))
      (node (ref "IC2") (pin "16") (pinfunction "USBDM_16") (pintype "bidirectional"))
    )
    (net (code "54") (name "Net-(IC2-USBDP)") (class "Default")
      (node (ref "CN3") (pin "D+") (pinfunction "D+_D+") (pintype "bidirectional"))
      (node (ref "IC2") (pin "15") (pinfunction "USBDP_15") (pintype "bidirectional"))
    )
    (net (code "55") (name "Net-(IC2-VCC)") (class "Default")
      (node (ref "CN3") (pin "VBUS") (pinfunction "VBUS_VBUS") (pintype "power_in"))
      (node (ref "IC2") (pin "20") (pinfunction "VCC_20") (pintype "power_in"))
      (node (ref "R22") (pin "2") (pinfunction "2_2") (pintype "passive"))
      (node (ref "R23") (pin "2") (pinfunction "2_2") (pintype "passive"))
    )
    (net (code "56") (name "Net-(K1-Pad1)") (class "Default")
      (node (ref "K1") (pin "1") (pinfunction "1_1") (pintype "passive"))
      (node (ref "K1") (pin "17") (pinfunction "17_17") (pintype "passive"))
      (node (ref "SJ1") (pin "1") (pinfunction "1_1") (pintype "passive"))
    )
    (net (code "57") (name "Net-(LED1-PadA)") (class "Default")
      (node (ref "LED1") (pin "A") (pinfunction "A_A") (pintype "passive"))
      (node (ref "R13") (pin "1") (pinfunction "1_1") (pintype "passive"))
    )
    (net (code "58") (name "Net-(LED2-PadA)") (class "Default")
      (node (ref "LED2") (pin "A") (pinfunction "A_A") (pintype "passive"))
      (node (ref "R16") (pin "1") (pinfunction "1_1") (pintype "passive"))
    )
    (net (code "59") (name "Net-(LED3-PadA)") (class "Default")
      (node (ref "LED3") (pin "A") (pinfunction "A_A") (pintype "passive"))
      (node (ref "R22") (pin "1") (pinfunction "1_1") (pintype "passive"))
    )
    (net (code "60") (name "Net-(LED4-PadA)") (class "Default")
      (node (ref "LED4") (pin "A") (pinfunction "A_A") (pintype "passive"))
      (node (ref "R23") (pin "1") (pinfunction "1_1") (pintype "passive"))
    )
    (net (code "61") (name "Net-(Q2-D)") (class "Default")
      (node (ref "JP1") (pin "PWR") (pinfunction "PWR_PWR") (pintype "bidirectional"))
      (node (ref "Q2") (pin "3") (pinfunction "D_3") (pintype "passive"))
      (node (ref "SJ4") (pin "1") (pinfunction "1_1") (pintype "passive"))
      (node (ref "U4") (pin "4") (pinfunction "E1_4") (pintype "passive"))
    )
    (net (code "62") (name "Net-(Q2-G)") (class "Default")
      (node (ref "Q2") (pin "1") (pinfunction "G_1") (pintype "passive"))
      (node (ref "R18") (pin "2") (pinfunction "2_2") (pintype "passive"))
      (node (ref "U4") (pin "6") (pinfunction "C2_6") (pintype "passive"))
    )
    (net (code "63") (name "Net-(R9-PadS)") (class "Default")
      (node (ref "R9") (pin "S") (pinfunction "S_S") (pintype "passive"))
      (node (ref "SV1") (pin "2") (pinfunction "2_2") (pintype "passive"))
    )
    (net (code "64") (name "Net-(SJ2-Pad1)") (class "Default")
      (node (ref "SJ2") (pin "1") (pinfunction "1_1") (pintype "passive"))
      (node (ref "SJ3") (pin "1") (pinfunction "1_1") (pintype "passive"))
      (node (ref "U$5") (pin "1") (pinfunction "1_1") (pintype "bidirectional"))
    )
    (net (code "65") (name "Net-(SJ2-Pad3)") (class "Default")
      (node (ref "SJ2") (pin "3") (pinfunction "3_3") (pintype "passive"))
      (node (ref "SJ3") (pin "3") (pinfunction "3_3") (pintype "passive"))
      (node (ref "U$5") (pin "2") (pinfunction "2_2") (pintype "bidirectional"))
    )
    (net (code "66") (name "Net-(U$1-SQW)") (class "Default")
      (node (ref "R5") (pin "1") (pinfunction "1_1") (pintype "passive"))
      (node (ref "U$1") (pin "7") (pinfunction "SQW_7") (pintype "bidirectional"))
    )
    (net (code "67") (name "Net-(U$1-X1)") (class "Default")
      (node (ref "U$1") (pin "1") (pinfunction "X1_1") (pintype "bidirectional"))
      (node (ref "Y1") (pin "X2") (pinfunction "2_X2") (pintype "passive"))
    )
    (net (code "68") (name "Net-(U$1-X2)") (class "Default")
      (node (ref "U$1") (pin "2") (pinfunction "X2_2") (pintype "bidirectional"))
      (node (ref "Y1") (pin "X1") (pinfunction "1_X1") (pintype "passive"))
    )
    (net (code "69") (name "Net-(U$4-A)") (class "Default")
      (node (ref "R15") (pin "2") (pinfunction "2_2") (pintype "passive"))
      (node (ref "SJ2") (pin "2") (pinfunction "2_2") (pintype "passive"))
      (node (ref "U$4") (pin "6") (pinfunction "A_6") (pintype "bidirectional"))
    )
    (net (code "70") (name "Net-(U$4-B)") (class "Default")
      (node (ref "R15") (pin "1") (pinfunction "1_1") (pintype "passive"))
      (node (ref "SJ3") (pin "2") (pinfunction "2_2") (pintype "passive"))
      (node (ref "U$4") (pin "7") (pinfunction "B_7") (pintype "bidirectional"))
    )
    (net (code "71") (name "Net-(U$6-IN)") (class "Default")
      (node (ref "CN2") (pin "VBUS") (pinfunction "VBUS_VBUS") (pintype "power_in"))
      (node (ref "U$6") (pin "2") (pinfunction "IN_2") (pintype "bidirectional"))
    )
    (net (code "72") (name "Net-(U$8-CBLUE)") (class "Default")
      (node (ref "R20") (pin "1") (pinfunction "1_1") (pintype "passive"))
      (node (ref "U$8") (pin "P$4") (pinfunction "CBLUE_P$4") (pintype "passive"))
    )
    (net (code "73") (name "Net-(U$8-CGREEN)") (class "Default")
      (node (ref "R21") (pin "1") (pinfunction "1_1") (pintype "passive"))
      (node (ref "U$8") (pin "P$3") (pinfunction "CGREEN_P$3") (pintype "passive"))
    )
    (net (code "74") (name "Net-(U$8-CRED)") (class "Default")
      (node (ref "R19") (pin "1") (pinfunction "1_1") (pintype "passive"))
      (node (ref "U$8") (pin "P$2") (pinfunction "CRED_P$2") (pintype "passive"))
    )
    (net (code "75") (name "Net-(U1-WP)") (class "Default")
      (node (ref "CFG") (pin "1") (pinfunction "1_1") (pintype "passive"))
      (node (ref "R3") (pin "1") (pinfunction "1_1") (pintype "passive"))
      (node (ref "U1") (pin "7") (pinfunction "WP_7") (pintype "input"))
    )
    (net (code "76") (name "Net-(U2-ALERT)") (class "Default")
      (node (ref "R4") (pin "1") (pinfunction "1_1") (pintype "passive"))
      (node (ref "U2") (pin "3") (pinfunction "ALERT_3") (pintype "bidirectional"))
    )
    (net (code "77") (name "Net-(U3-A1)") (class "Default")
      (node (ref "R9") (pin "E") (pinfunction "E_E") (pintype "passive"))
      (node (ref "U3") (pin "1") (pinfunction "A1_1") (pintype "passive"))
    )
    (net (code "78") (name "Net-(U3-W1)") (class "Default")
      (node (ref "SV1") (pin "1") (pinfunction "1_1") (pintype "passive"))
      (node (ref "U3") (pin "2") (pinfunction "W1_2") (pintype "passive"))
    )
    (net (code "79") (name "Net-(U4-B1)") (class "Default")
      (node (ref "R17") (pin "2") (pinfunction "2_2") (pintype "passive"))
      (node (ref "U4") (pin "2") (pinfunction "B2_2") (pintype "passive"))
      (node (ref "U4") (pin "3") (pinfunction "C1_3") (pintype "passive"))
      (node (ref "U4") (pin "5") (pinfunction "B1_5") (pintype "passive"))
    )
    (net (code "80") (name "Net-(U5-OUT)") (class "Default")
      (node (ref "SJ1") (pin "3") (pinfunction "3_3") (pintype "passive"))
      (node (ref "U5") (pin "3") (pinfunction "OUT_3") (pintype "output"))
    )
    (net (code "81") (name "unconnected-(CN1-PadID)") (class "Default")
      (node (ref "CN1") (pin "ID") (pinfunction "ID_ID") (pintype "bidirectional"))
    )
    (net (code "82") (name "unconnected-(CN2-PadID)") (class "Default")
      (node (ref "CN2") (pin "ID") (pinfunction "ID_ID") (pintype "bidirectional"))
    )
    (net (code "83") (name "unconnected-(CN3-PadID)") (class "Default")
      (node (ref "CN3") (pin "ID") (pinfunction "ID_ID") (pintype "bidirectional"))
    )
    (net (code "84") (name "unconnected-(IC1-ADC6-Pad19)") (class "Default")
      (node (ref "IC1") (pin "19") (pinfunction "ADC6_19") (pintype "bidirectional"))
    )
    (net (code "85") (name "unconnected-(IC1-ADC7-Pad22)") (class "Default")
      (node (ref "IC1") (pin "22") (pinfunction "ADC7_22") (pintype "bidirectional"))
    )
    (net (code "86") (name "unconnected-(IC1-PB2(SS{slash}OC1B)-Pad14)") (class "Default")
      (node (ref "IC1") (pin "14") (pinfunction "PB2(SS/OC1B)_14") (pintype "bidirectional"))
    )
    (net (code "87") (name "unconnected-(IC1-PC1(ADC1)-Pad24)") (class "Default")
      (node (ref "IC1") (pin "24") (pinfunction "PC1(ADC1)_24") (pintype "bidirectional"))
    )
    (net (code "88") (name "unconnected-(IC1-PC2(ADC2)-Pad25)") (class "Default")
      (node (ref "IC1") (pin "25") (pinfunction "PC2(ADC2)_25") (pintype "bidirectional"))
    )
    (net (code "89") (name "unconnected-(IC1-PC3(ADC3)-Pad26)") (class "Default")
      (node (ref "IC1") (pin "26") (pinfunction "PC3(ADC3)_26") (pintype "bidirectional"))
    )
    (net (code "90") (name "unconnected-(IC1-PC5(ADC5{slash}SCL)-Pad28)") (class "Default")
      (node (ref "IC1") (pin "28") (pinfunction "PC5(ADC5/SCL)_28") (pintype "bidirectional"))
    )
    (net (code "91") (name "unconnected-(IC1-PD0(RXD)-Pad30)") (class "Default")
      (node (ref "IC1") (pin "30") (pinfunction "PD0(RXD)_30") (pintype "bidirectional"))
    )
    (net (code "92") (name "unconnected-(IC1-PD4(XCK{slash}T0)-Pad2)") (class "Default")
      (node (ref "IC1") (pin "2") (pinfunction "PD4(XCK/T0)_2") (pintype "bidirectional"))
    )
    (net (code "93") (name "unconnected-(IC1-PD5(T1)-Pad9)") (class "Default")
      (node (ref "IC1") (pin "9") (pinfunction "PD5(T1)_9") (pintype "bidirectional"))
    )
    (net (code "94") (name "unconnected-(IC1-PD6(AIN0)-Pad10)") (class "Default")
      (node (ref "IC1") (pin "10") (pinfunction "PD6(AIN0)_10") (pintype "bidirectional"))
    )
    (net (code "95") (name "unconnected-(IC1-PD7(AIN1)-Pad11)") (class "Default")
      (node (ref "IC1") (pin "11") (pinfunction "PD7(AIN1)_11") (pintype "bidirectional"))
    )
    (net (code "96") (name "unconnected-(IC2-3V3OUT-Pad17)") (class "Default")
      (node (ref "IC2") (pin "17") (pinfunction "3V3OUT_17") (pintype "output"))
    )
    (net (code "97") (name "unconnected-(IC2-CBUS2-Pad13)") (class "Default")
      (node (ref "IC2") (pin "13") (pinfunction "CBUS2_13") (pintype "bidirectional"))
    )
    (net (code "98") (name "unconnected-(IC2-CBUS3-Pad14)") (class "Default")
      (node (ref "IC2") (pin "14") (pinfunction "CBUS3_14") (pintype "bidirectional"))
    )
    (net (code "99") (name "unconnected-(IC2-CBUS4-Pad12)") (class "Default")
      (node (ref "IC2") (pin "12") (pinfunction "CBUS4_12") (pintype "bidirectional"))
    )
    (net (code "100") (name "unconnected-(IC2-OSCI-Pad27)") (class "Default")
      (node (ref "IC2") (pin "27") (pinfunction "OSCI_27") (pintype "input"))
    )
    (net (code "101") (name "unconnected-(IC2-OSCO-Pad28)") (class "Default")
      (node (ref "IC2") (pin "28") (pinfunction "OSCO_28") (pintype "output"))
    )
    (net (code "102") (name "unconnected-(IC2-~{CTS}-Pad11)") (class "Default")
      (node (ref "IC2") (pin "11") (pinfunction "~{CTS}_11") (pintype "input"))
    )
    (net (code "103") (name "unconnected-(IC2-~{DCD}-Pad10)") (class "Default")
      (node (ref "IC2") (pin "10") (pinfunction "~{DCD}_10") (pintype "input"))
    )
    (net (code "104") (name "unconnected-(IC2-~{DSR}-Pad9)") (class "Default")
      (node (ref "IC2") (pin "9") (pinfunction "~{DSR}_9") (pintype "input"))
    )
    (net (code "105") (name "unconnected-(IC2-~{DTR}-Pad2)") (class "Default")
      (node (ref "IC2") (pin "2") (pinfunction "~{DTR}_2") (pintype "output"))
    )
    (net (code "106") (name "unconnected-(IC2-~{RESET}-Pad19)") (class "Default")
      (node (ref "IC2") (pin "19") (pinfunction "~{RESET}_19") (pintype "input"))
    )
    (net (code "107") (name "unconnected-(IC2-~{RI}-Pad6)") (class "Default")
      (node (ref "IC2") (pin "6") (pinfunction "~{RI}_6") (pintype "input"))
    )
    (net (code "108") (name "unconnected-(IC2-~{RTS}-Pad3)") (class "Default")
      (node (ref "IC2") (pin "3") (pinfunction "~{RTS}_3") (pintype "output"))
    )
    (net (code "109") (name "unconnected-(R9-PadA)") (class "Default")
      (node (ref "R9") (pin "A") (pinfunction "A_A") (pintype "passive"))
    )
    (net (code "110") (name "unconnected-(U$4-RO-Pad1)") (class "Default")
      (node (ref "U$4") (pin "1") (pinfunction "RO_1") (pintype "bidirectional"))
    )
    (net (code "111") (name "unconnected-(U$5-Pad3)") (class "Default")
      (node (ref "U$5") (pin "3") (pinfunction "3_3") (pintype "bidirectional"))
    )
    (net (code "112") (name "unconnected-(U$5-Pad4)") (class "Default")
      (node (ref "U$5") (pin "4") (pinfunction "4_4") (pintype "bidirectional"))
    )
    (net (code "113") (name "unconnected-(U$5-Pad5)") (class "Default")
      (node (ref "U$5") (pin "5") (pinfunction "5_5") (pintype "bidirectional"))
    )
    (net (code "114") (name "unconnected-(U$5-Pad6)") (class "Default")
      (node (ref "U$5") (pin "6") (pinfunction "6_6") (pintype "bidirectional"))
    )
    (net (code "115") (name "unconnected-(U3-B1-Pad3)") (class "Default")
      (node (ref "U3") (pin "3") (pinfunction "B1_3") (pintype "passive"))
    )
    (net (code "116") (name "unconnected-(U3-NC-Pad13)") (class "Default")
      (node (ref "U3") (pin "13") (pinfunction "NC_13") (pintype "passive"))
    )
    (net (code "117") (name "unconnected-(U3-O1-Pad14)") (class "Default")
      (node (ref "U3") (pin "14") (pinfunction "O1_14") (pintype "passive"))
    )
    (net (code "118") (name "unconnected-(U3-O2-Pad12)") (class "Default")
      (node (ref "U3") (pin "12") (pinfunction "O2_12") (pintype "passive"))
    )
  )
)
